# Synch_demod.net
KiCad netlist of a schematic drawn in Altium Designer
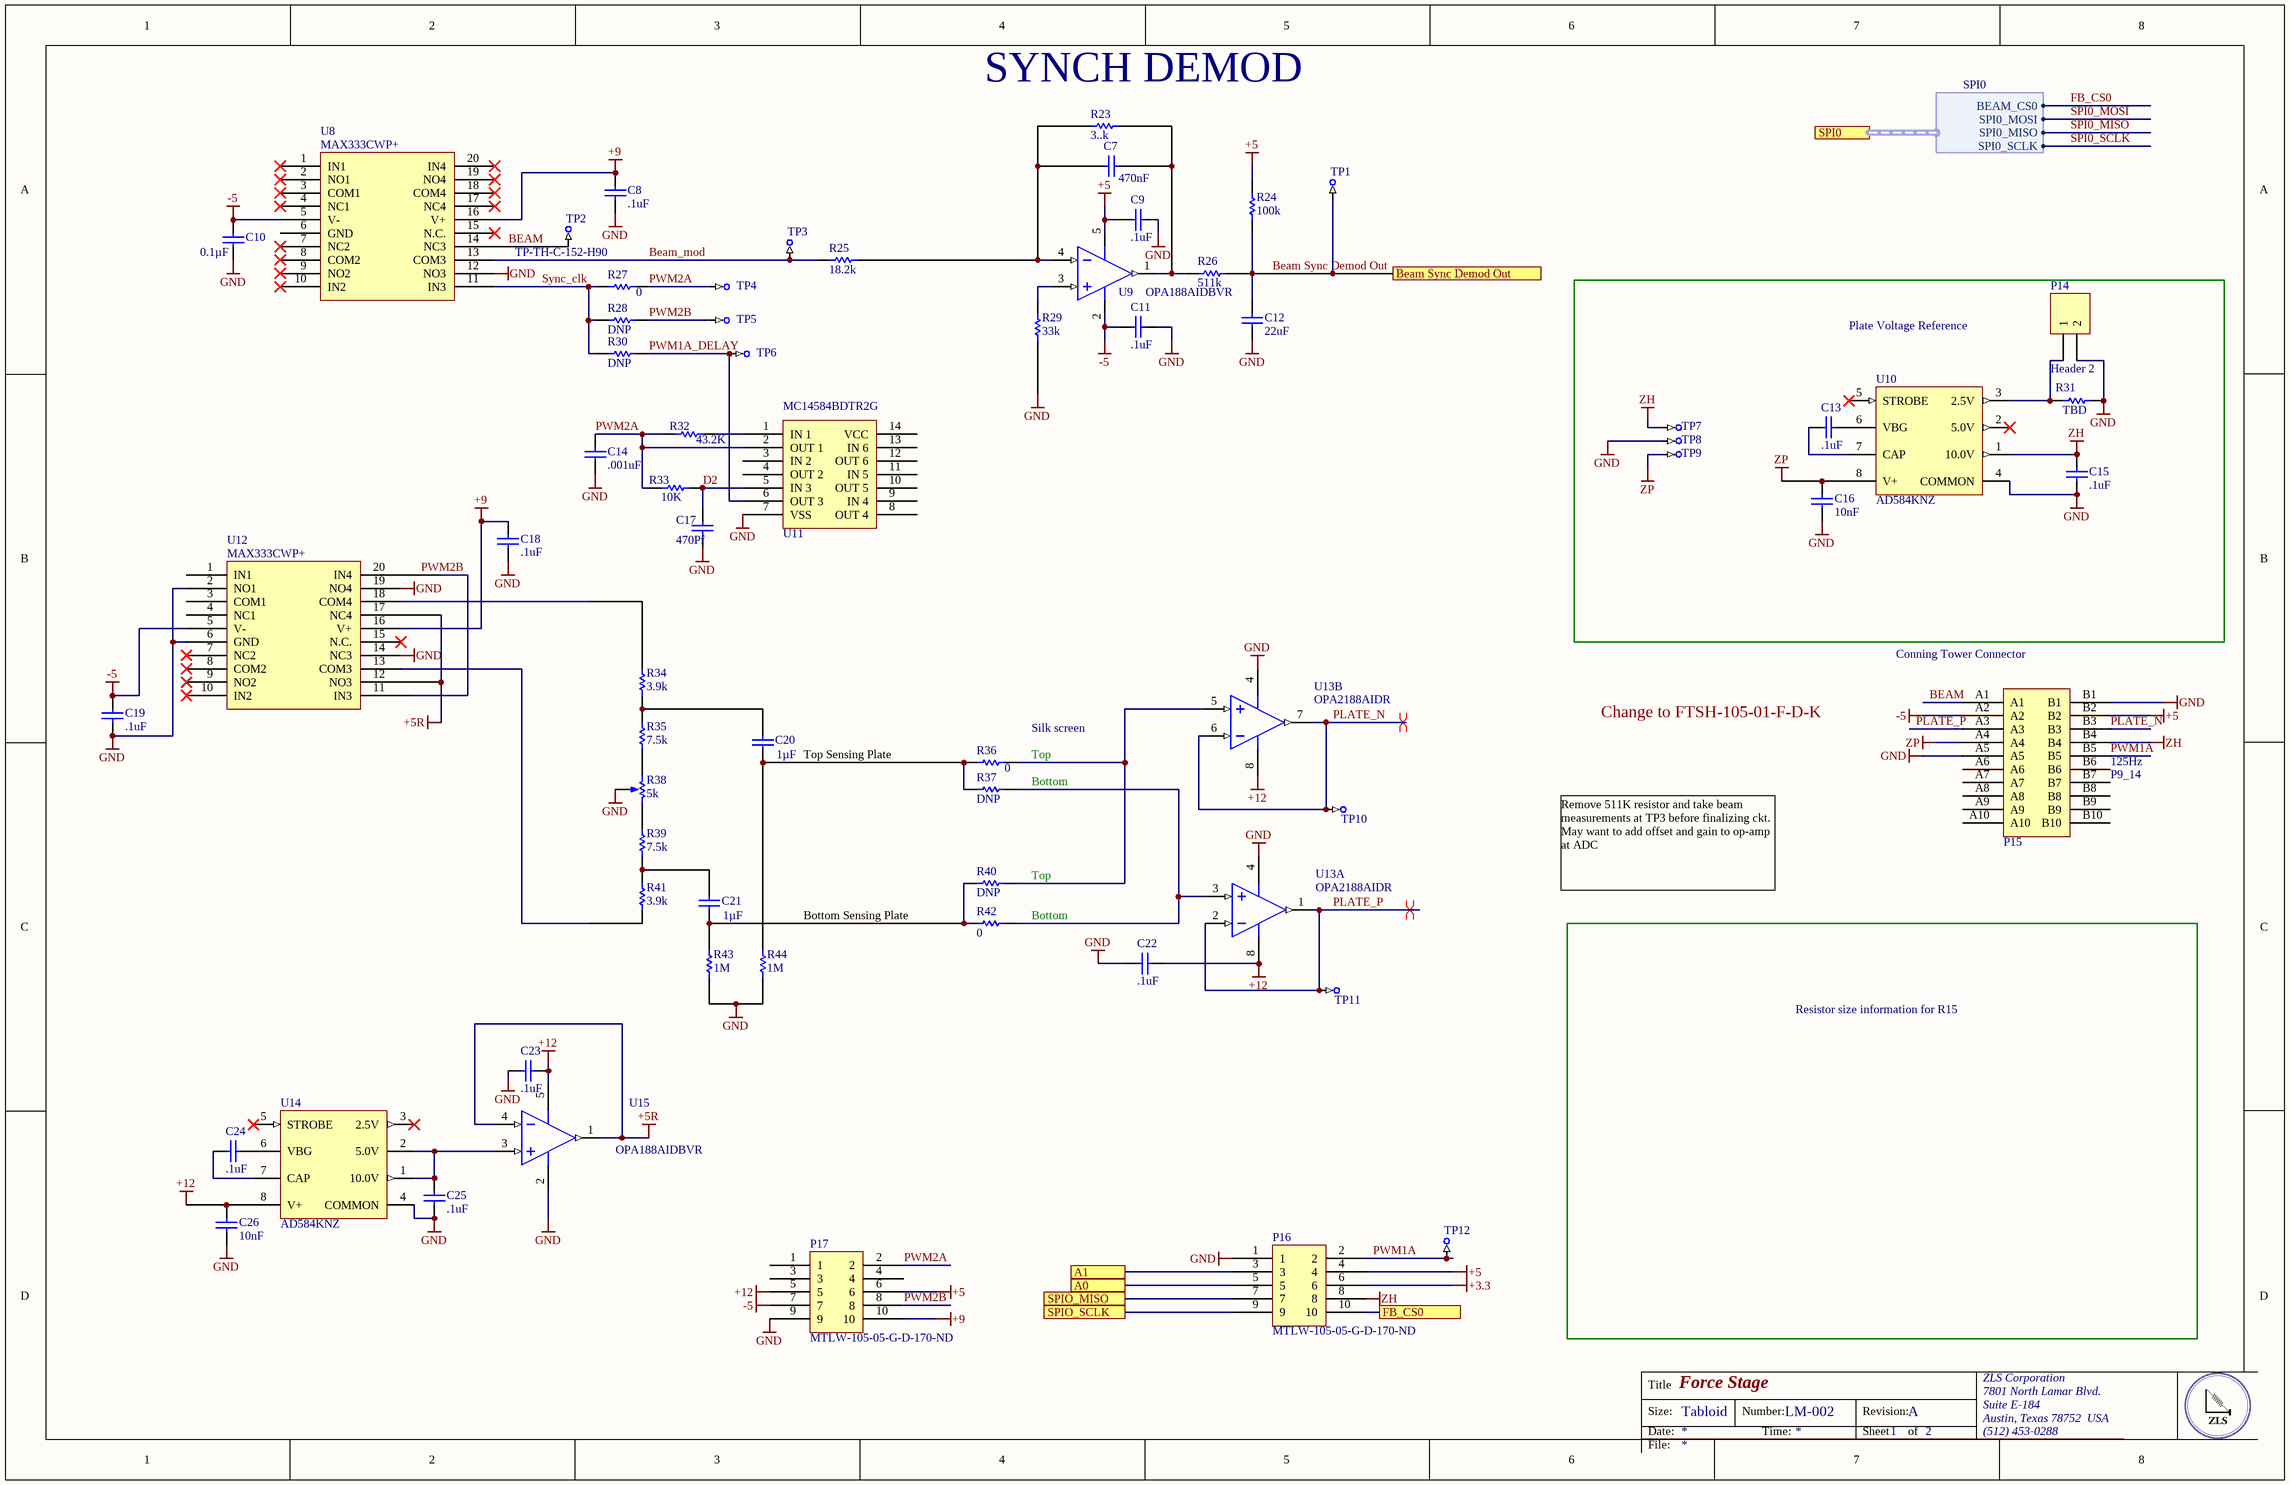
[diagram p0: Synch_demod.SchDoc]

(export (version "E")
  (design (tool "Eeschema 10.0.6"))
  (components
    (comp (ref "C7")
      (value "470nF")
      (footprint "CAPC0805(2012)75_L")
      (description "CAP 150pF 16V ±10% 0805 (2012 Metric) Thickness 0.75mm SMD")
      (fields (field (name "TOLERANCE") "Â±10%"))
      (libsource (lib "Altium Content Vault") (part "CMP-1036-02117-1"))
    )
    (comp (ref "C8")
      (value ".1uF")
      (footprint "CAPC0805(2012)75_L")
      (description "CAP 150pF 16V ±10% 0805 (2012 Metric) Thickness 0.75mm SMD")
      (fields (field (name "TOLERANCE") "Â±10%"))
      (libsource (lib "Altium Content Vault") (part "CMP-1036-02117-1"))
    )
    (comp (ref "C9")
      (value ".1uF")
      (footprint "CAPC0805(2012)75_L")
      (description "CAP 150pF 16V ±10% 0805 (2012 Metric) Thickness 0.75mm SMD")
      (fields (field (name "TOLERANCE") "Â±10%"))
      (libsource (lib "Altium Content Vault") (part "CMP-1036-02117-1"))
    )
    (comp (ref "C10")
      (value "CAP CER 0.1UF 25V X7R 0805")
      (footprint "CAPC0805(2012)145_N")
      (fields
        (field (name "MANUFACTURER") "Murata Electronics North America")
        (field (name "MANUFACTURER PART NUMBER") "GRM21BR71E104KA01L")
        (field (name "CAPACITANCE") "0.1µF")
        (field (name "TOLERANCE") "±10%")
      )
      (libsource (lib "Altium Content Vault") (part "CMP-1036-04795-1"))
    )
    (comp (ref "C11")
      (value ".1uF")
      (footprint "CAPC0805(2012)75_L")
      (description "CAP 150pF 16V ±10% 0805 (2012 Metric) Thickness 0.75mm SMD")
      (fields (field (name "TOLERANCE") "Â±10%"))
      (libsource (lib "Altium Content Vault") (part "CMP-1036-02117-1"))
    )
    (comp (ref "C12")
      (value "22uF")
      (footprint "CAPC0805(2012)75_L")
      (description "CAP 150pF 16V ±10% 0805 (2012 Metric) Thickness 0.75mm SMD")
      (fields (field (name "TOLERANCE") "Â±10%"))
      (libsource (lib "Altium Content Vault") (part "CMP-1036-02117-1"))
    )
    (comp (ref "C13")
      (value ".1uF")
      (footprint "CAPC0805(2012)75_M")
      (description "CAP 33pF 25V ±2% 0805 (2012 Metric) Thickness 0.75mm SMD")
      (fields (field (name "TOLERANCE") "Â±2%"))
      (libsource (lib "Altium Content Vault") (part "CMP-1036-01414-1"))
    )
    (comp (ref "C14")
      (value ".001uF")
      (footprint "CAPC0805(2012)75_L")
      (description "CAP 150pF 16V ±10% 0805 (2012 Metric) Thickness 0.75mm SMD")
      (fields (field (name "TOLERANCE") "Â±10%"))
      (libsource (lib "Altium Content Vault") (part "CMP-1036-02117-1"))
    )
    (comp (ref "C15")
      (value ".1uF")
      (footprint "CAPC0805(2012)75_M")
      (description "CAP 33pF 25V ±2% 0805 (2012 Metric) Thickness 0.75mm SMD")
      (fields (field (name "TOLERANCE") "Â±2%"))
      (libsource (lib "Altium Content Vault") (part "CMP-1036-01414-1"))
    )
    (comp (ref "C16")
      (value "Multilayer Ceramic Capacitors MLCC - SMD/SMT 0.01uF 50volts 10% X7R")
      (footprint "CAPC0805(2012)145_N")
      (fields
        (field (name "MANUFACTURER") "Kemet")
        (field (name "MANUFACTURER PART NUMBER") "C0805C103K5RACAUTO")
        (field (name "CAPACITANCE") "10nF")
        (field (name "TOLERANCE") "10%")
      )
      (libsource (lib "Altium Content Vault") (part "CMP-1036-04795-1"))
    )
    (comp (ref "C17")
      (value "470Pf")
      (footprint "CAPC0805(2012)75_L")
      (description "CAP 150pF 16V ±10% 0805 (2012 Metric) Thickness 0.75mm SMD")
      (fields (field (name "TOLERANCE") "Â±10%"))
      (libsource (lib "Altium Content Vault") (part "CMP-1036-02117-1"))
    )
    (comp (ref "C18")
      (value ".1uF")
      (footprint "CAPC0805(2012)75_M")
      (description "CAP 33pF 25V ±2% 0805 (2012 Metric) Thickness 0.75mm SMD")
      (fields (field (name "TOLERANCE") "Â±2%"))
      (libsource (lib "Altium Content Vault") (part "CMP-1036-01414-1"))
    )
    (comp (ref "C19")
      (value ".1uF")
      (footprint "CAPC0805(2012)75_M")
      (description "CAP 33pF 25V ±2% 0805 (2012 Metric) Thickness 0.75mm SMD")
      (fields (field (name "TOLERANCE") "Â±2%"))
      (libsource (lib "Altium Content Vault") (part "CMP-1036-01414-1"))
    )
    (comp (ref "C20")
      (value "CAP CER 1UF 25V X7R 0805")
      (footprint "CAPC0805(2012)155_L")
      (fields
        (field (name "MANUFACTURER") "Murata Electronics North America")
        (field (name "MANUFACTURER PART NUMBER") "GRM21BR71E105KA99L")
        (field (name "CAPACITANCE") "1µF")
        (field (name "TOLERANCE") "±10%")
      )
      (libsource (lib "Altium Content Vault") (part "CMP-1036-04882-1"))
    )
    (comp (ref "C21")
      (value "CAP CER 1UF 25V X7R 0805")
      (footprint "CAPC0805(2012)155_L")
      (fields
        (field (name "MANUFACTURER") "Murata Electronics North America")
        (field (name "MANUFACTURER PART NUMBER") "GRM21BR71E105KA99L")
        (field (name "CAPACITANCE") "1µF")
        (field (name "TOLERANCE") "±10%")
      )
      (libsource (lib "Altium Content Vault") (part "CMP-1036-04882-1"))
    )
    (comp (ref "C22")
      (value ".1uF")
      (footprint "CAPC0805(2012)75_M")
      (description "CAP 33pF 25V ±2% 0805 (2012 Metric) Thickness 0.75mm SMD")
      (fields (field (name "TOLERANCE") "Â±2%"))
      (libsource (lib "Altium Content Vault") (part "CMP-1036-01414-1"))
    )
    (comp (ref "C23")
      (value ".1uF")
      (footprint "CAPC0805(2012)75_M")
      (description "CAP 33pF 25V ±2% 0805 (2012 Metric) Thickness 0.75mm SMD")
      (fields (field (name "TOLERANCE") "Â±2%"))
      (libsource (lib "Altium Content Vault") (part "CMP-1036-01414-1"))
    )
    (comp (ref "C24")
      (value ".1uF")
      (footprint "CAPC0805(2012)75_M")
      (description "CAP 33pF 25V ±2% 0805 (2012 Metric) Thickness 0.75mm SMD")
      (fields (field (name "TOLERANCE") "Â±2%"))
      (libsource (lib "Altium Content Vault") (part "CMP-1036-01414-1"))
    )
    (comp (ref "C25")
      (value ".1uF")
      (footprint "CAPC0805(2012)75_M")
      (description "CAP 33pF 25V ±2% 0805 (2012 Metric) Thickness 0.75mm SMD")
      (fields (field (name "TOLERANCE") "Â±2%"))
      (libsource (lib "Altium Content Vault") (part "CMP-1036-01414-1"))
    )
    (comp (ref "C26")
      (value "Multilayer Ceramic Capacitors MLCC - SMD/SMT 0.01uF 50volts 10% X7R")
      (footprint "CAPC0805(2012)145_N")
      (fields
        (field (name "MANUFACTURER") "Kemet")
        (field (name "MANUFACTURER PART NUMBER") "C0805C103K5RACAUTO")
        (field (name "CAPACITANCE") "10nF")
        (field (name "TOLERANCE") "10%")
      )
      (libsource (lib "Altium Content Vault") (part "CMP-1036-04795-1"))
    )
    (comp (ref "P14")
      (value "Header 2")
      (footprint "HDR1X2")
      (description "Header, 2-Pin")
      (fields (field (name "PUBLISHER") "Altium Limited"))
      (libsource (lib "Miscellaneous Connectors") (part "Header 2"))
    )
    (comp (ref "P15")
      (value "MEC6-110-0-PCB")
      (footprint "MEC6-110-02-L-DV")
      (libsource (lib "ZLS_Schematic_lib") (part "MEC6-110-0-PCB"))
    )
    (comp (ref "P16")
      (value "TLW-105-05-G-D")
      (footprint "TLW-105-05-G-D")
      (fields
        (field (name "SUPPLIER PART NUMBER 1") "MTLW-105-05-G-D-170-ND")
        (field (name "MANUFACTURER") "Samtec Inc.")
        (field (name "MANUFACTURER PART NUMBER") "MTLW-105-05-G-D-170")
      )
      (libsource (lib "ZLS_Schematic_lib") (part "TLW-105-05-G-D"))
    )
    (comp (ref "P17")
      (value "TLW-105-05-G-D")
      (footprint "TLW-105-05-G-D")
      (fields
        (field (name "SUPPLIER PART NUMBER 1") "MTLW-105-05-G-D-170-ND")
        (field (name "MANUFACTURER") "Samtec Inc.")
        (field (name "MANUFACTURER PART NUMBER") "MTLW-105-05-G-D-170")
      )
      (libsource (lib "ZLS_Schematic_lib") (part "TLW-105-05-G-D"))
    )
    (comp (ref "R23")
      (value "3..k")
      (footprint "RESC0805(2012)_L")
      (description "2R55 0.125W 1% 0805 (2012 Metric)  SMD")
      (fields (field (name "TOLERANCE") "1 %") (field (name "POWER") "0.125 W"))
      (libsource (lib "Altium Content Vault") (part "CMP-1013-00215-1"))
    )
    (comp (ref "R24")
      (value "100k")
      (footprint "RESC0805(2012)_L")
      (description "2R55 0.125W 1% 0805 (2012 Metric)  SMD")
      (fields (field (name "TOLERANCE") "1 %") (field (name "POWER") "0.125 W"))
      (libsource (lib "Altium Content Vault") (part "CMP-1013-00215-1"))
    )
    (comp (ref "R25")
      (value "18.2k")
      (footprint "RESC0805(2012)_L")
      (description "2R55 0.125W 1% 0805 (2012 Metric)  SMD")
      (fields (field (name "TOLERANCE") "1 %") (field (name "POWER") "0.125 W"))
      (libsource (lib "Altium Content Vault") (part "CMP-1013-00215-1"))
    )
    (comp (ref "R26")
      (value "511k")
      (footprint "RESC0805(2012)_L")
      (description "2R55 0.125W 1% 0805 (2012 Metric)  SMD")
      (fields (field (name "TOLERANCE") "1 %") (field (name "POWER") "0.125 W"))
      (libsource (lib "Altium Content Vault") (part "CMP-1013-00215-1"))
    )
    (comp (ref "R27")
      (value "0")
      (footprint "RESC0805(2012)_L")
      (description "2R55 0.125W 1% 0805 (2012 Metric)  SMD")
      (fields (field (name "TOLERANCE") "1 %") (field (name "POWER") "0.125 W"))
      (libsource (lib "Altium Content Vault") (part "CMP-1013-00215-1"))
    )
    (comp (ref "R28")
      (value "DNP")
      (footprint "RESC0805(2012)_L")
      (description "2R55 0.125W 1% 0805 (2012 Metric)  SMD")
      (fields (field (name "TOLERANCE") "1 %") (field (name "POWER") "0.125 W"))
      (libsource (lib "Altium Content Vault") (part "CMP-1013-00215-1"))
    )
    (comp (ref "R29")
      (value "33k")
      (footprint "RESC0805(2012)_L")
      (description "2R55 0.125W 1% 0805 (2012 Metric)  SMD")
      (fields (field (name "TOLERANCE") "1 %") (field (name "POWER") "0.125 W"))
      (libsource (lib "Altium Content Vault") (part "CMP-1013-00215-1"))
    )
    (comp (ref "R30")
      (value "DNP")
      (footprint "RESC0805(2012)_L")
      (description "2R55 0.125W 1% 0805 (2012 Metric)  SMD")
      (fields (field (name "TOLERANCE") "1 %") (field (name "POWER") "0.125 W"))
      (libsource (lib "Altium Content Vault") (part "CMP-1013-00215-1"))
    )
    (comp (ref "R31")
      (value "TBD")
      (footprint "VH102K")
      (libsource (lib "altium-import") (part "root_0_CMP-1013-00393-1_"))
    )
    (comp (ref "R32")
      (value "43.2K")
      (footprint "RESC0805(2012)_L")
      (description "2R55 0.125W 1% 0805 (2012 Metric)  SMD")
      (fields (field (name "TOLERANCE") "1 %") (field (name "POWER") "0.125 W"))
      (libsource (lib "Altium Content Vault") (part "CMP-1013-00215-1"))
    )
    (comp (ref "R33")
      (value "10K")
      (footprint "RESC0805(2012)_L")
      (description "2R55 0.125W 1% 0805 (2012 Metric)  SMD")
      (fields (field (name "TOLERANCE") "1 %") (field (name "POWER") "0.125 W"))
      (libsource (lib "Altium Content Vault") (part "CMP-1013-00215-1"))
    )
    (comp (ref "R34")
      (value "3.9k")
      (footprint "RESC0805(2012)_L")
      (description "2R55 0.125W 1% 0805 (2012 Metric)  SMD")
      (fields (field (name "TOLERANCE") "1 %") (field (name "POWER") "0.125 W"))
      (libsource (lib "Altium Content Vault") (part "CMP-1013-00215-1"))
    )
    (comp (ref "R35")
      (value "7.5k")
      (footprint "RESC0805(2012)_L")
      (description "2R55 0.125W 1% 0805 (2012 Metric)  SMD")
      (fields (field (name "TOLERANCE") "1 %") (field (name "POWER") "0.125 W"))
      (libsource (lib "Altium Content Vault") (part "CMP-1013-00215-1"))
    )
    (comp (ref "R36")
      (value "0")
      (footprint "RESC0805(2012)_L")
      (description "2R55 0.125W 1% 0805 (2012 Metric)  SMD")
      (fields (field (name "TOLERANCE") "1 %") (field (name "POWER") "0.125 W"))
      (libsource (lib "Altium Content Vault") (part "CMP-1013-00215-1"))
    )
    (comp (ref "R37")
      (value "DNP")
      (footprint "RESC0805(2012)_L")
      (description "2R55 0.125W 1% 0805 (2012 Metric)  SMD")
      (fields (field (name "TOLERANCE") "1 %") (field (name "POWER") "0.125 W"))
      (libsource (lib "Altium Content Vault") (part "CMP-1013-00215-1"))
    )
    (comp (ref "R38")
      (value "TRIMMER 5K OHM 0.25W PC PIN")
      (footprint "Trimmer 2.54")
      (fields
        (field (name "MANUFACTURER") "Vishay Foil Resistors (Division of Vishay Precision Group)")
        (field (name "MANUFACTURER PART NUMBER") "Y00535K00000J0L")
        (field (name "RESISTANCE (OHMS)") "5k")
        (field (name "TOLERANCE") "±5%")
      )
      (libsource (lib "ZLS_Schematic_lib") (part "Trimmer"))
    )
    (comp (ref "R39")
      (value "7.5k")
      (footprint "RESC0805(2012)_L")
      (description "2R55 0.125W 1% 0805 (2012 Metric)  SMD")
      (fields (field (name "TOLERANCE") "1 %") (field (name "POWER") "0.125 W"))
      (libsource (lib "Altium Content Vault") (part "CMP-1013-00215-1"))
    )
    (comp (ref "R40")
      (value "DNP")
      (footprint "RESC0805(2012)_L")
      (description "2R55 0.125W 1% 0805 (2012 Metric)  SMD")
      (fields (field (name "TOLERANCE") "1 %") (field (name "POWER") "0.125 W"))
      (libsource (lib "Altium Content Vault") (part "CMP-1013-00215-1"))
    )
    (comp (ref "R41")
      (value "3.9k")
      (footprint "RESC0805(2012)_L")
      (description "2R55 0.125W 1% 0805 (2012 Metric)  SMD")
      (fields (field (name "TOLERANCE") "1 %") (field (name "POWER") "0.125 W"))
      (libsource (lib "Altium Content Vault") (part "CMP-1013-00215-1"))
    )
    (comp (ref "R42")
      (value "0")
      (footprint "RESC0805(2012)_L")
      (description "2R55 0.125W 1% 0805 (2012 Metric)  SMD")
      (fields (field (name "TOLERANCE") "1 %") (field (name "POWER") "0.125 W"))
      (libsource (lib "Altium Content Vault") (part "CMP-1013-00215-1"))
    )
    (comp (ref "R43")
      (value "1M")
      (footprint "RESC0805(2012)_L")
      (description "2R55 0.125W 1% 0805 (2012 Metric)  SMD")
      (fields (field (name "TOLERANCE") "1 %") (field (name "POWER") "0.125 W"))
      (libsource (lib "Altium Content Vault") (part "CMP-1013-00215-1"))
    )
    (comp (ref "R44")
      (value "1M")
      (footprint "RESC0805(2012)_L")
      (description "2R55 0.125W 1% 0805 (2012 Metric)  SMD")
      (fields (field (name "TOLERANCE") "1 %") (field (name "POWER") "0.125 W"))
      (libsource (lib "Altium Content Vault") (part "CMP-1013-00215-1"))
    )
    (comp (ref "TP1")
      (value "TP-TH-C-152-H90")
      (footprint "TP-TH-C-152-H90")
      (description "Test Point, Through Hole, Hole Size 0.9 mm, PCB Mount with Silkscreen Box")
      (fields (field (name "MANUFACTURER") "No Vendor"))
      (libsource (lib "Altium Content Vault") (part "CMP-0484-00003-2"))
    )
    (comp (ref "TP2")
      (value "TP-TH-C-152-H90")
      (footprint "TP-TH-C-152-H90")
      (description "Test Point, Through Hole, Hole Size 0.9 mm, PCB Mount with Silkscreen Box")
      (fields (field (name "MANUFACTURER") "No Vendor"))
      (libsource (lib "Altium Content Vault") (part "TP-TH"))
    )
    (comp (ref "TP3")
      (value "TP-TH-C-152-H90")
      (footprint "TP-TH-C-152-H90")
      (description "Test Point, Through Hole, Hole Size 0.9 mm, PCB Mount with Silkscreen Box")
      (fields (field (name "MANUFACTURER") "No Vendor"))
      (libsource (lib "Altium Content Vault") (part "CMP-0484-00003-2"))
    )
    (comp (ref "TP4")
      (value "TP-TH-C-152-H90")
      (footprint "TP-TH-C-152-H90")
      (description "Test Point, Through Hole, Hole Size 0.9 mm, PCB Mount with Silkscreen Box")
      (fields (field (name "MANUFACTURER") "No Vendor"))
      (libsource (lib "Altium Content Vault") (part "CMP-0484-00003-2"))
    )
    (comp (ref "TP5")
      (value "TP-TH-C-152-H90")
      (footprint "TP-TH-C-152-H90")
      (description "Test Point, Through Hole, Hole Size 0.9 mm, PCB Mount with Silkscreen Box")
      (fields (field (name "MANUFACTURER") "No Vendor"))
      (libsource (lib "Altium Content Vault") (part "CMP-0484-00003-2"))
    )
    (comp (ref "TP6")
      (value "TP-TH-C-152-H90")
      (footprint "TP-TH-C-152-H90")
      (description "Test Point, Through Hole, Hole Size 0.9 mm, PCB Mount with Silkscreen Box")
      (fields (field (name "MANUFACTURER") "No Vendor"))
      (libsource (lib "Altium Content Vault") (part "CMP-0484-00003-2"))
    )
    (comp (ref "TP7")
      (value "TP-TH-C-152-H90")
      (footprint "TP-TH-C-152-H90")
      (description "Test Point, Through Hole, Hole Size 0.9 mm, PCB Mount with Silkscreen Box")
      (fields (field (name "MANUFACTURER") "No Vendor"))
      (libsource (lib "Altium Content Vault") (part "CMP-0484-00003-2"))
    )
    (comp (ref "TP8")
      (value "TP-TH-C-152-H90")
      (footprint "TP-TH-C-152-H90")
      (description "Test Point, Through Hole, Hole Size 0.9 mm, PCB Mount with Silkscreen Box")
      (fields (field (name "MANUFACTURER") "No Vendor"))
      (libsource (lib "Altium Content Vault") (part "CMP-0484-00003-2"))
    )
    (comp (ref "TP9")
      (value "TP-TH-C-152-H90")
      (footprint "TP-TH-C-152-H90")
      (description "Test Point, Through Hole, Hole Size 0.9 mm, PCB Mount with Silkscreen Box")
      (fields (field (name "MANUFACTURER") "No Vendor"))
      (libsource (lib "Altium Content Vault") (part "CMP-0484-00003-2"))
    )
    (comp (ref "TP10")
      (value "TP-TH-C-152-H90")
      (footprint "TP-TH-C-152-H90")
      (description "Test Point, Through Hole, Hole Size 0.9 mm, PCB Mount with Silkscreen Box")
      (fields (field (name "MANUFACTURER") "No Vendor"))
      (libsource (lib "Altium Content Vault") (part "CMP-0484-00003-2"))
    )
    (comp (ref "TP11")
      (value "TP-TH-C-152-H90")
      (footprint "TP-TH-C-152-H90")
      (description "Test Point, Through Hole, Hole Size 0.9 mm, PCB Mount with Silkscreen Box")
      (fields (field (name "MANUFACTURER") "No Vendor"))
      (libsource (lib "Altium Content Vault") (part "CMP-0484-00003-2"))
    )
    (comp (ref "TP12")
      (value "TP-TH-C-152-H90")
      (footprint "TP-TH-C-152-H90")
      (description "Test Point, Through Hole, Hole Size 0.9 mm, PCB Mount with Silkscreen Box")
      (fields (field (name "MANUFACTURER") "No Vendor"))
      (libsource (lib "Altium Content Vault") (part "CMP-0484-00003-2"))
    )
    (comp (ref "U8")
      (value "MAX333CWP+")
      (footprint "TSOP65P640X90-20N")
      (description "IC SWITCH QUAD SPDT 20TSSOP")
      (fields (field (name "MANUFACTURER") "Maxim") (field (name "MANUFACTURER PART NUMBER") "MAX333AEUP+"))
      (libsource (lib "ZLS_Schematic_lib") (part "MAX333CWP+"))
    )
    (comp (ref "U9")
      (value "OPA188AIDBVR")
      (footprint "DBV0005A_M")
      (fields (field (name "MANUFACTURER") "Texas Instruments"))
      (libsource (lib "Altium Content Vault") (part "CMP-0809-00005-2"))
    )
    (comp (ref "U10")
      (value "AD584KNZ")
      (footprint "ADI-N-8")
      (fields (field (name "MANUFACTURER") "Analog Devices"))
      (libsource (lib "Altium Content Vault") (part "ADI-AD584-N-8"))
    )
    (comp (ref "U11")
      (value "MC14584BDTR2G")
      (footprint "MC14584BDTR2G")
      (fields (field (name "MANUFACTURER") "ON Semiconductor") (field (name "BASE PART NUMBER") "4584"))
      (libsource (lib "ZLS_Schematic_lib") (part "MC14584BDTR2G"))
    )
    (comp (ref "U12")
      (value "MAX333CWP+")
      (footprint "TSOP65P640X90-20N")
      (description "IC SWITCH QUAD SPDT 20TSSOP")
      (fields (field (name "MANUFACTURER") "Maxim") (field (name "MANUFACTURER PART NUMBER") "MAX333AEUP+"))
      (libsource (lib "ZLS_Schematic_lib") (part "MAX333CWP+"))
    )
    (comp (ref "U13")
      (value "OPA2188AIDR")
      (footprint "D0008A_L")
      (fields (field (name "MANUFACTURER") "Texas Instruments"))
      (libsource (lib "Altium Content Vault") (part "CMP-0272-00241-3"))
    )
    (comp (ref "U14")
      (value "AD584KNZ")
      (footprint "ADI-N-8")
      (fields (field (name "MANUFACTURER") "Analog Devices"))
      (libsource (lib "Altium Content Vault") (part "CMP-0784-00054-1"))
    )
    (comp (ref "U15")
      (value "OPA188AIDBVR")
      (footprint "DBV0005A_M")
      (fields (field (name "MANUFACTURER") "Texas Instruments"))
      (libsource (lib "Altium Content Vault") (part "CMP-0809-00005-2"))
    )
  )
  (nets
    (net (code "2") (name "+3.3") (class "Default")
      (node (ref "P16") (pin "6") (pinfunction "6_6") (pintype "passive"))
    )
    (net (code "3") (name "+5") (class "Default")
      (node (ref "C9") (pin "1") (pinfunction "1_1") (pintype "passive"))
      (node (ref "P15") (pin "B2") (pinfunction "B2_B2") (pintype "passive"))
      (node (ref "P16") (pin "4") (pinfunction "4_4") (pintype "passive"))
      (node (ref "P17") (pin "6") (pinfunction "6_6") (pintype "passive"))
      (node (ref "R24") (pin "2") (pinfunction "2_2") (pintype "passive"))
      (node (ref "U9") (pin "5") (pinfunction "V+_5") (pintype "power_in"))
    )
    (net (code "4") (name "+5R") (class "Default")
      (node (ref "U12") (pin "12") (pinfunction "NO3_12") (pintype "passive"))
      (node (ref "U12") (pin "17") (pinfunction "NC4_17") (pintype "passive"))
      (node (ref "U15") (pin "1") (pinfunction "OUT_1") (pintype "output"))
      (node (ref "U15") (pin "4") (pinfunction "IN-_4") (pintype "input"))
    )
    (net (code "5") (name "+9") (class "Default")
      (node (ref "C18") (pin "2") (pinfunction "2_2") (pintype "passive"))
      (node (ref "C8") (pin "2") (pinfunction "2_2") (pintype "passive"))
      (node (ref "P17") (pin "10") (pinfunction "10_10") (pintype "passive"))
      (node (ref "U12") (pin "16") (pinfunction "V+_16") (pintype "power_in"))
      (node (ref "U8") (pin "16") (pinfunction "V+_16") (pintype "power_in"))
    )
    (net (code "6") (name "+12") (class "Default")
      (node (ref "C22") (pin "2") (pinfunction "2_2") (pintype "passive"))
      (node (ref "C23") (pin "2") (pinfunction "2_2") (pintype "passive"))
      (node (ref "C26") (pin "1") (pinfunction "1_1") (pintype "passive"))
      (node (ref "P17") (pin "5") (pinfunction "5_5") (pintype "passive"))
      (node (ref "U13") (pin "8") (pinfunction "V+_8") (pintype "power_in"))
      (node (ref "U14") (pin "8") (pinfunction "V+_8") (pintype "power_in"))
      (node (ref "U15") (pin "5") (pinfunction "V+_5") (pintype "power_in"))
    )
    (net (code "7") (name "-5") (class "Default")
      (node (ref "C10") (pin "1") (pinfunction "1_1") (pintype "passive"))
      (node (ref "C11") (pin "1") (pinfunction "1_1") (pintype "passive"))
      (node (ref "C19") (pin "2") (pinfunction "2_2") (pintype "passive"))
      (node (ref "P15") (pin "A2") (pinfunction "A2_A2") (pintype "passive"))
      (node (ref "P17") (pin "7") (pinfunction "7_7") (pintype "passive"))
      (node (ref "U12") (pin "5") (pinfunction "V-_5") (pintype "power_in"))
      (node (ref "U8") (pin "5") (pinfunction "V-_5") (pintype "power_in"))
      (node (ref "U9") (pin "2") (pinfunction "V-_2") (pintype "power_in"))
    )
    (net (code "8") (name "/A0") (class "Default")
      (node (ref "P16") (pin "5") (pinfunction "5_5") (pintype "passive"))
    )
    (net (code "9") (name "/A1") (class "Default")
      (node (ref "P16") (pin "3") (pinfunction "3_3") (pintype "passive"))
    )
    (net (code "10") (name "/BEAM") (class "Default")
      (node (ref "P15") (pin "A1") (pinfunction "A1_A1") (pintype "passive"))
      (node (ref "TP2") (pin "1") (pinfunction "1_1") (pintype "input"))
      (node (ref "U8") (pin "14") (pinfunction "NC3_14") (pintype "passive"))
    )
    (net (code "11") (name "/Beam Sync Demod Out") (class "Default")
      (node (ref "C12") (pin "2") (pinfunction "2_2") (pintype "passive"))
      (node (ref "R24") (pin "1") (pinfunction "1_1") (pintype "passive"))
      (node (ref "R26") (pin "1") (pinfunction "1_1") (pintype "passive"))
      (node (ref "TP1") (pin "1") (pinfunction "1_1") (pintype "input"))
    )
    (net (code "12") (name "/Beam_mod") (class "Default")
      (node (ref "R25") (pin "2") (pinfunction "2_2") (pintype "passive"))
      (node (ref "TP3") (pin "1") (pinfunction "1_1") (pintype "input"))
      (node (ref "U8") (pin "13") (pinfunction "COM3_13") (pintype "passive"))
    )
    (net (code "13") (name "/D2") (class "Default")
      (node (ref "C17") (pin "2") (pinfunction "2_2") (pintype "passive"))
      (node (ref "R33") (pin "1") (pinfunction "1_1") (pintype "passive"))
      (node (ref "U11") (pin "5") (pinfunction "IN_3_5") (pintype "passive"))
    )
    (net (code "14") (name "/FB_CS0") (class "Default")
      (node (ref "P16") (pin "10") (pinfunction "10_10") (pintype "passive"))
    )
    (net (code "15") (name "/PLATE_N") (class "Default")
      (node (ref "P15") (pin "B3") (pinfunction "B3_B3") (pintype "passive"))
      (node (ref "TP10") (pin "1") (pinfunction "1_1") (pintype "input"))
      (node (ref "U13") (pin "6") (pinfunction "IN_B-_6") (pintype "input"))
      (node (ref "U13") (pin "7") (pinfunction "OUT_B_7") (pintype "output"))
    )
    (net (code "16") (name "/PLATE_P") (class "Default")
      (node (ref "P15") (pin "A3") (pinfunction "A3_A3") (pintype "passive"))
      (node (ref "TP11") (pin "1") (pinfunction "1_1") (pintype "input"))
      (node (ref "U13") (pin "1") (pinfunction "OUT_A_1") (pintype "output"))
      (node (ref "U13") (pin "2") (pinfunction "IN_A-_2") (pintype "input"))
    )
    (net (code "17") (name "/PWM1A") (class "Default")
      (node (ref "P15") (pin "B5") (pinfunction "B5_B5") (pintype "passive"))
      (node (ref "P16") (pin "2") (pinfunction "2_2") (pintype "passive"))
      (node (ref "TP12") (pin "1") (pinfunction "1_1") (pintype "input"))
    )
    (net (code "18") (name "/PWM1A_DELAY") (class "Default")
      (node (ref "R30") (pin "1") (pinfunction "1_1") (pintype "passive"))
      (node (ref "TP6") (pin "1") (pinfunction "1_1") (pintype "input"))
      (node (ref "U11") (pin "6") (pinfunction "OUT_3_6") (pintype "passive"))
    )
    (net (code "19") (name "/PWM2A") (class "Default")
      (node (ref "C14") (pin "2") (pinfunction "2_2") (pintype "passive"))
      (node (ref "P17") (pin "2") (pinfunction "2_2") (pintype "passive"))
      (node (ref "R27") (pin "1") (pinfunction "1_1") (pintype "passive"))
      (node (ref "R32") (pin "2") (pinfunction "2_2") (pintype "passive"))
      (node (ref "R33") (pin "2") (pinfunction "2_2") (pintype "passive"))
      (node (ref "TP4") (pin "1") (pinfunction "1_1") (pintype "input"))
      (node (ref "U11") (pin "2") (pinfunction "OUT_1_2") (pintype "passive"))
    )
    (net (code "20") (name "/PWM2B") (class "Default")
      (node (ref "P17") (pin "8") (pinfunction "8_8") (pintype "passive"))
      (node (ref "R28") (pin "1") (pinfunction "1_1") (pintype "passive"))
      (node (ref "TP5") (pin "1") (pinfunction "1_1") (pintype "input"))
      (node (ref "U12") (pin "11") (pinfunction "IN3_11") (pintype "passive"))
      (node (ref "U12") (pin "20") (pinfunction "IN4_20") (pintype "passive"))
    )
    (net (code "24") (name "/SPIO_MISO") (class "Default")
      (node (ref "P16") (pin "7") (pinfunction "7_7") (pintype "passive"))
    )
    (net (code "25") (name "/SPIO_SCLK") (class "Default")
      (node (ref "P16") (pin "9") (pinfunction "9_9") (pintype "passive"))
    )
    (net (code "26") (name "/Sync_clk") (class "Default")
      (node (ref "R27") (pin "2") (pinfunction "2_2") (pintype "passive"))
      (node (ref "R28") (pin "2") (pinfunction "2_2") (pintype "passive"))
      (node (ref "R30") (pin "2") (pinfunction "2_2") (pintype "passive"))
      (node (ref "U8") (pin "11") (pinfunction "IN3_11") (pintype "passive"))
    )
    (net (code "28") (name "GND") (class "Default")
      (node (ref "C10") (pin "2") (pinfunction "2_2") (pintype "passive"))
      (node (ref "C11") (pin "2") (pinfunction "2_2") (pintype "passive"))
      (node (ref "C12") (pin "1") (pinfunction "1_1") (pintype "passive"))
      (node (ref "C14") (pin "1") (pinfunction "1_1") (pintype "passive"))
      (node (ref "C15") (pin "1") (pinfunction "1_1") (pintype "passive"))
      (node (ref "C16") (pin "2") (pinfunction "2_2") (pintype "passive"))
      (node (ref "C17") (pin "1") (pinfunction "1_1") (pintype "passive"))
      (node (ref "C18") (pin "1") (pinfunction "1_1") (pintype "passive"))
      (node (ref "C19") (pin "1") (pinfunction "1_1") (pintype "passive"))
      (node (ref "C22") (pin "1") (pinfunction "1_1") (pintype "passive"))
      (node (ref "C23") (pin "1") (pinfunction "1_1") (pintype "passive"))
      (node (ref "C25") (pin "1") (pinfunction "1_1") (pintype "passive"))
      (node (ref "C26") (pin "2") (pinfunction "2_2") (pintype "passive"))
      (node (ref "C8") (pin "1") (pinfunction "1_1") (pintype "passive"))
      (node (ref "C9") (pin "2") (pinfunction "2_2") (pintype "passive"))
      (node (ref "P14") (pin "2") (pinfunction "2_2") (pintype "passive"))
      (node (ref "P15") (pin "A5") (pinfunction "A5_A5") (pintype "passive"))
      (node (ref "P15") (pin "B1") (pinfunction "B1_B1") (pintype "passive"))
      (node (ref "P16") (pin "1") (pinfunction "1_1") (pintype "passive"))
      (node (ref "P17") (pin "9") (pinfunction "9_9") (pintype "passive"))
      (node (ref "R29") (pin "1") (pinfunction "1_1") (pintype "passive"))
      (node (ref "R31") (pin "2") (pinfunction "2_2") (pintype "passive"))
      (node (ref "R38") (pin "2") (pinfunction "b_2") (pintype "passive"))
      (node (ref "R43") (pin "1") (pinfunction "1_1") (pintype "passive"))
      (node (ref "R44") (pin "1") (pinfunction "1_1") (pintype "passive"))
      (node (ref "TP8") (pin "1") (pinfunction "1_1") (pintype "input"))
      (node (ref "U10") (pin "4") (pinfunction "COMMON_4") (pintype "passive"))
      (node (ref "U11") (pin "7") (pinfunction "VSS_7") (pintype "passive"))
      (node (ref "U12") (pin "14") (pinfunction "NC3_14") (pintype "passive"))
      (node (ref "U12") (pin "19") (pinfunction "NO4_19") (pintype "passive"))
      (node (ref "U12") (pin "2") (pinfunction "NO1_2") (pintype "passive"))
      (node (ref "U12") (pin "6") (pinfunction "GND_6") (pintype "passive"))
      (node (ref "U13") (pin "4") (pinfunction "V-_4") (pintype "power_in"))
      (node (ref "U14") (pin "4") (pinfunction "COMMON_4") (pintype "passive"))
      (node (ref "U15") (pin "2") (pinfunction "V-_2") (pintype "power_in"))
      (node (ref "U8") (pin "12") (pinfunction "NO3_12") (pintype "passive"))
    )
    (net (code "29") (name "Net-(C20-Pad1)") (class "Default")
      (node (ref "C20") (pin "1") (pinfunction "1_1") (pintype "passive"))
      (node (ref "R36") (pin "2") (pinfunction "2_2") (pintype "passive"))
      (node (ref "R37") (pin "2") (pinfunction "2_2") (pintype "passive"))
      (node (ref "R44") (pin "2") (pinfunction "2_2") (pintype "passive"))
    )
    (net (code "30") (name "Net-(C20-Pad2)") (class "Default")
      (node (ref "C20") (pin "2") (pinfunction "2_2") (pintype "passive"))
      (node (ref "R34") (pin "1") (pinfunction "1_1") (pintype "passive"))
      (node (ref "R35") (pin "2") (pinfunction "2_2") (pintype "passive"))
    )
    (net (code "31") (name "Net-(C21-Pad1)") (class "Default")
      (node (ref "C21") (pin "1") (pinfunction "1_1") (pintype "passive"))
      (node (ref "R40") (pin "2") (pinfunction "2_2") (pintype "passive"))
      (node (ref "R42") (pin "2") (pinfunction "2_2") (pintype "passive"))
      (node (ref "R43") (pin "2") (pinfunction "2_2") (pintype "passive"))
    )
    (net (code "32") (name "Net-(C21-Pad2)") (class "Default")
      (node (ref "C21") (pin "2") (pinfunction "2_2") (pintype "passive"))
      (node (ref "R39") (pin "1") (pinfunction "1_1") (pintype "passive"))
      (node (ref "R41") (pin "2") (pinfunction "2_2") (pintype "passive"))
    )
    (net (code "33") (name "Net-(R38-a)") (class "Default")
      (node (ref "R35") (pin "1") (pinfunction "1_1") (pintype "passive"))
      (node (ref "R38") (pin "1") (pinfunction "a_1") (pintype "passive"))
    )
    (net (code "34") (name "Net-(R38-c)") (class "Default")
      (node (ref "R38") (pin "3") (pinfunction "c_3") (pintype "passive"))
      (node (ref "R39") (pin "2") (pinfunction "2_2") (pintype "passive"))
    )
    (net (code "35") (name "Net-(U9-IN+)") (class "Default")
      (node (ref "R29") (pin "2") (pinfunction "2_2") (pintype "passive"))
      (node (ref "U9") (pin "3") (pinfunction "IN+_3") (pintype "input"))
    )
    (net (code "36") (name "Net-(U9-IN-)") (class "Default")
      (node (ref "C7") (pin "1") (pinfunction "1_1") (pintype "passive"))
      (node (ref "R23") (pin "2") (pinfunction "2_2") (pintype "passive"))
      (node (ref "R25") (pin "1") (pinfunction "1_1") (pintype "passive"))
      (node (ref "U9") (pin "4") (pinfunction "IN-_4") (pintype "input"))
    )
    (net (code "37") (name "Net-(U9-OUT)") (class "Default")
      (node (ref "C7") (pin "2") (pinfunction "2_2") (pintype "passive"))
      (node (ref "R23") (pin "1") (pinfunction "1_1") (pintype "passive"))
      (node (ref "R26") (pin "2") (pinfunction "2_2") (pintype "passive"))
      (node (ref "U9") (pin "1") (pinfunction "OUT_1") (pintype "output"))
    )
    (net (code "38") (name "Net-(U10-2.5V)") (class "Default")
      (node (ref "P14") (pin "1") (pinfunction "1_1") (pintype "passive"))
      (node (ref "R31") (pin "1") (pinfunction "1_1") (pintype "passive"))
      (node (ref "U10") (pin "3") (pinfunction "2.5V_3") (pintype "output"))
    )
    (net (code "39") (name "Net-(U10-CAP)") (class "Default")
      (node (ref "C13") (pin "1") (pinfunction "1_1") (pintype "passive"))
      (node (ref "U10") (pin "7") (pinfunction "CAP_7") (pintype "passive"))
    )
    (net (code "40") (name "Net-(U10-VBG)") (class "Default")
      (node (ref "C13") (pin "2") (pinfunction "2_2") (pintype "passive"))
      (node (ref "U10") (pin "6") (pinfunction "VBG_6") (pintype "passive"))
    )
    (net (code "41") (name "Net-(U11-IN_1)") (class "Default")
      (node (ref "R32") (pin "1") (pinfunction "1_1") (pintype "passive"))
      (node (ref "U11") (pin "1") (pinfunction "IN_1_1") (pintype "passive"))
    )
    (net (code "42") (name "Net-(U12-COM3)") (class "Default")
      (node (ref "R41") (pin "1") (pinfunction "1_1") (pintype "passive"))
      (node (ref "U12") (pin "13") (pinfunction "COM3_13") (pintype "passive"))
    )
    (net (code "43") (name "Net-(U12-COM4)") (class "Default")
      (node (ref "R34") (pin "2") (pinfunction "2_2") (pintype "passive"))
      (node (ref "U12") (pin "18") (pinfunction "COM4_18") (pintype "passive"))
    )
    (net (code "44") (name "Net-(U13A-IN_A+)") (class "Default")
      (node (ref "R37") (pin "1") (pinfunction "1_1") (pintype "passive"))
      (node (ref "R42") (pin "1") (pinfunction "1_1") (pintype "passive"))
      (node (ref "U13") (pin "3") (pinfunction "IN_A+_3") (pintype "input"))
    )
    (net (code "45") (name "Net-(U13B-IN_B+)") (class "Default")
      (node (ref "R36") (pin "1") (pinfunction "1_1") (pintype "passive"))
      (node (ref "R40") (pin "1") (pinfunction "1_1") (pintype "passive"))
      (node (ref "U13") (pin "5") (pinfunction "IN_B+_5") (pintype "input"))
    )
    (net (code "46") (name "Net-(U14-10.0V)") (class "Default")
      (node (ref "C25") (pin "2") (pinfunction "2_2") (pintype "passive"))
      (node (ref "U14") (pin "1") (pinfunction "10.0V_1") (pintype "output"))
      (node (ref "U14") (pin "2") (pinfunction "5.0V_2") (pintype "passive"))
      (node (ref "U15") (pin "3") (pinfunction "IN+_3") (pintype "input"))
    )
    (net (code "47") (name "Net-(U14-CAP)") (class "Default")
      (node (ref "C24") (pin "1") (pinfunction "1_1") (pintype "passive"))
      (node (ref "U14") (pin "7") (pinfunction "CAP_7") (pintype "passive"))
    )
    (net (code "48") (name "Net-(U14-VBG)") (class "Default")
      (node (ref "C24") (pin "2") (pinfunction "2_2") (pintype "passive"))
      (node (ref "U14") (pin "6") (pinfunction "VBG_6") (pintype "passive"))
    )
    (net (code "49") (name "ZH") (class "Default")
      (node (ref "C15") (pin "2") (pinfunction "2_2") (pintype "passive"))
      (node (ref "P15") (pin "B4") (pinfunction "B4_B4") (pintype "passive"))
      (node (ref "P16") (pin "8") (pinfunction "8_8") (pintype "passive"))
      (node (ref "TP7") (pin "1") (pinfunction "1_1") (pintype "input"))
      (node (ref "U10") (pin "1") (pinfunction "10.0V_1") (pintype "output"))
    )
    (net (code "50") (name "ZP") (class "Default")
      (node (ref "C16") (pin "1") (pinfunction "1_1") (pintype "passive"))
      (node (ref "P15") (pin "A4") (pinfunction "A4_A4") (pintype "passive"))
      (node (ref "TP9") (pin "1") (pinfunction "1_1") (pintype "input"))
      (node (ref "U10") (pin "8") (pinfunction "V+_8") (pintype "power_in"))
    )
    (net (code "51") (name "unconnected-(P15-PadA6)") (class "Default")
      (node (ref "P15") (pin "A6") (pinfunction "A6_A6") (pintype "passive"))
    )
    (net (code "52") (name "unconnected-(P15-PadA7)") (class "Default")
      (node (ref "P15") (pin "A7") (pinfunction "A7_A7") (pintype "passive"))
    )
    (net (code "53") (name "unconnected-(P15-PadA8)") (class "Default")
      (node (ref "P15") (pin "A8") (pinfunction "A8_A8") (pintype "passive"))
    )
    (net (code "54") (name "unconnected-(P15-PadA9)") (class "Default")
      (node (ref "P15") (pin "A9") (pinfunction "A9_A9") (pintype "passive"))
    )
    (net (code "55") (name "unconnected-(P15-PadA10)") (class "Default")
      (node (ref "P15") (pin "A10") (pinfunction "A10_A10") (pintype "passive"))
    )
    (net (code "56") (name "unconnected-(P15-PadB6)") (class "Default")
      (node (ref "P15") (pin "B6") (pinfunction "B6_B6") (pintype "passive"))
    )
    (net (code "57") (name "unconnected-(P15-PadB7)") (class "Default")
      (node (ref "P15") (pin "B7") (pinfunction "B7_B7") (pintype "passive"))
    )
    (net (code "58") (name "unconnected-(P15-PadB8)") (class "Default")
      (node (ref "P15") (pin "B8") (pinfunction "B8_B8") (pintype "passive"))
    )
    (net (code "59") (name "unconnected-(P15-PadB9)") (class "Default")
      (node (ref "P15") (pin "B9") (pinfunction "B9_B9") (pintype "passive"))
    )
    (net (code "60") (name "unconnected-(P15-PadB10)") (class "Default")
      (node (ref "P15") (pin "B10") (pinfunction "B10_B10") (pintype "passive"))
    )
    (net (code "61") (name "unconnected-(P17-Pad1)") (class "Default")
      (node (ref "P17") (pin "1") (pinfunction "1_1") (pintype "passive"))
    )
    (net (code "62") (name "unconnected-(P17-Pad3)") (class "Default")
      (node (ref "P17") (pin "3") (pinfunction "3_3") (pintype "passive"))
    )
    (net (code "63") (name "unconnected-(P17-Pad4)") (class "Default")
      (node (ref "P17") (pin "4") (pinfunction "4_4") (pintype "passive"))
    )
    (net (code "64") (name "unconnected-(U8-COM1-Pad3)") (class "Default")
      (node (ref "U8") (pin "3") (pinfunction "COM1_3") (pintype "passive+no_connect"))
    )
    (net (code "65") (name "unconnected-(U8-COM2-Pad8)") (class "Default")
      (node (ref "U8") (pin "8") (pinfunction "COM2_8") (pintype "passive+no_connect"))
    )
    (net (code "66") (name "unconnected-(U8-COM4-Pad18)") (class "Default")
      (node (ref "U8") (pin "18") (pinfunction "COM4_18") (pintype "passive+no_connect"))
    )
    (net (code "67") (name "unconnected-(U8-GND-Pad6)") (class "Default")
      (node (ref "U8") (pin "6") (pinfunction "GND_6") (pintype "passive"))
    )
    (net (code "68") (name "unconnected-(U8-IN1-Pad1)") (class "Default")
      (node (ref "U8") (pin "1") (pinfunction "IN1_1") (pintype "passive+no_connect"))
    )
    (net (code "69") (name "unconnected-(U8-IN2-Pad10)") (class "Default")
      (node (ref "U8") (pin "10") (pinfunction "IN2_10") (pintype "passive+no_connect"))
    )
    (net (code "70") (name "unconnected-(U8-IN4-Pad20)") (class "Default")
      (node (ref "U8") (pin "20") (pinfunction "IN4_20") (pintype "passive+no_connect"))
    )
    (net (code "71") (name "unconnected-(U8-N.C.-Pad15)") (class "Default")
      (node (ref "U8") (pin "15") (pinfunction "N.C._15") (pintype "passive+no_connect"))
    )
    (net (code "72") (name "unconnected-(U8-NC1-Pad4)") (class "Default")
      (node (ref "U8") (pin "4") (pinfunction "NC1_4") (pintype "passive+no_connect"))
    )
    (net (code "73") (name "unconnected-(U8-NC2-Pad7)") (class "Default")
      (node (ref "U8") (pin "7") (pinfunction "NC2_7") (pintype "passive+no_connect"))
    )
    (net (code "74") (name "unconnected-(U8-NC4-Pad17)") (class "Default")
      (node (ref "U8") (pin "17") (pinfunction "NC4_17") (pintype "passive+no_connect"))
    )
    (net (code "75") (name "unconnected-(U8-NO1-Pad2)") (class "Default")
      (node (ref "U8") (pin "2") (pinfunction "NO1_2") (pintype "passive+no_connect"))
    )
    (net (code "76") (name "unconnected-(U8-NO2-Pad9)") (class "Default")
      (node (ref "U8") (pin "9") (pinfunction "NO2_9") (pintype "passive+no_connect"))
    )
    (net (code "77") (name "unconnected-(U8-NO4-Pad19)") (class "Default")
      (node (ref "U8") (pin "19") (pinfunction "NO4_19") (pintype "passive+no_connect"))
    )
    (net (code "78") (name "unconnected-(U10-5.0V-Pad2)") (class "Default")
      (node (ref "U10") (pin "2") (pinfunction "5.0V_2") (pintype "output+no_connect"))
    )
    (net (code "79") (name "unconnected-(U10-STROBE-Pad5)") (class "Default")
      (node (ref "U10") (pin "5") (pinfunction "STROBE_5") (pintype "input+no_connect"))
    )
    (net (code "80") (name "unconnected-(U11-IN_2-Pad3)") (class "Default")
      (node (ref "U11") (pin "3") (pinfunction "IN_2_3") (pintype "passive"))
    )
    (net (code "81") (name "unconnected-(U11-IN_4-Pad9)") (class "Default")
      (node (ref "U11") (pin "9") (pinfunction "IN_4_9") (pintype "passive"))
    )
    (net (code "82") (name "unconnected-(U11-IN_5-Pad11)") (class "Default")
      (node (ref "U11") (pin "11") (pinfunction "IN_5_11") (pintype "passive"))
    )
    (net (code "83") (name "unconnected-(U11-IN_6-Pad13)") (class "Default")
      (node (ref "U11") (pin "13") (pinfunction "IN_6_13") (pintype "passive"))
    )
    (net (code "84") (name "unconnected-(U11-OUT_2-Pad4)") (class "Default")
      (node (ref "U11") (pin "4") (pinfunction "OUT_2_4") (pintype "passive"))
    )
    (net (code "85") (name "unconnected-(U11-OUT_4-Pad8)") (class "Default")
      (node (ref "U11") (pin "8") (pinfunction "OUT_4_8") (pintype "passive"))
    )
    (net (code "86") (name "unconnected-(U11-OUT_5-Pad10)") (class "Default")
      (node (ref "U11") (pin "10") (pinfunction "OUT_5_10") (pintype "passive"))
    )
    (net (code "87") (name "unconnected-(U11-OUT_6-Pad12)") (class "Default")
      (node (ref "U11") (pin "12") (pinfunction "OUT_6_12") (pintype "passive"))
    )
    (net (code "88") (name "unconnected-(U11-VCC-Pad14)") (class "Default")
      (node (ref "U11") (pin "14") (pinfunction "VCC_14") (pintype "passive"))
    )
    (net (code "89") (name "unconnected-(U12-COM1-Pad3)") (class "Default")
      (node (ref "U12") (pin "3") (pinfunction "COM1_3") (pintype "passive"))
    )
    (net (code "90") (name "unconnected-(U12-COM2-Pad8)") (class "Default")
      (node (ref "U12") (pin "8") (pinfunction "COM2_8") (pintype "passive+no_connect"))
    )
    (net (code "91") (name "unconnected-(U12-IN1-Pad1)") (class "Default")
      (node (ref "U12") (pin "1") (pinfunction "IN1_1") (pintype "passive"))
    )
    (net (code "92") (name "unconnected-(U12-IN2-Pad10)") (class "Default")
      (node (ref "U12") (pin "10") (pinfunction "IN2_10") (pintype "passive+no_connect"))
    )
    (net (code "93") (name "unconnected-(U12-N.C.-Pad15)") (class "Default")
      (node (ref "U12") (pin "15") (pinfunction "N.C._15") (pintype "passive+no_connect"))
    )
    (net (code "94") (name "unconnected-(U12-NC1-Pad4)") (class "Default")
      (node (ref "U12") (pin "4") (pinfunction "NC1_4") (pintype "passive"))
    )
    (net (code "95") (name "unconnected-(U12-NC2-Pad7)") (class "Default")
      (node (ref "U12") (pin "7") (pinfunction "NC2_7") (pintype "passive+no_connect"))
    )
    (net (code "96") (name "unconnected-(U12-NO2-Pad9)") (class "Default")
      (node (ref "U12") (pin "9") (pinfunction "NO2_9") (pintype "passive+no_connect"))
    )
    (net (code "97") (name "unconnected-(U14-2.5V-Pad3)") (class "Default")
      (node (ref "U14") (pin "3") (pinfunction "2.5V_3") (pintype "output+no_connect"))
    )
    (net (code "98") (name "unconnected-(U14-STROBE-Pad5)") (class "Default")
      (node (ref "U14") (pin "5") (pinfunction "STROBE_5") (pintype "input+no_connect"))
    )
  )
)
